# TCC_modulo_de_automa_o_Wifi_Rev_2.net
KiCad netlist of a schematic drawn in EAGLE
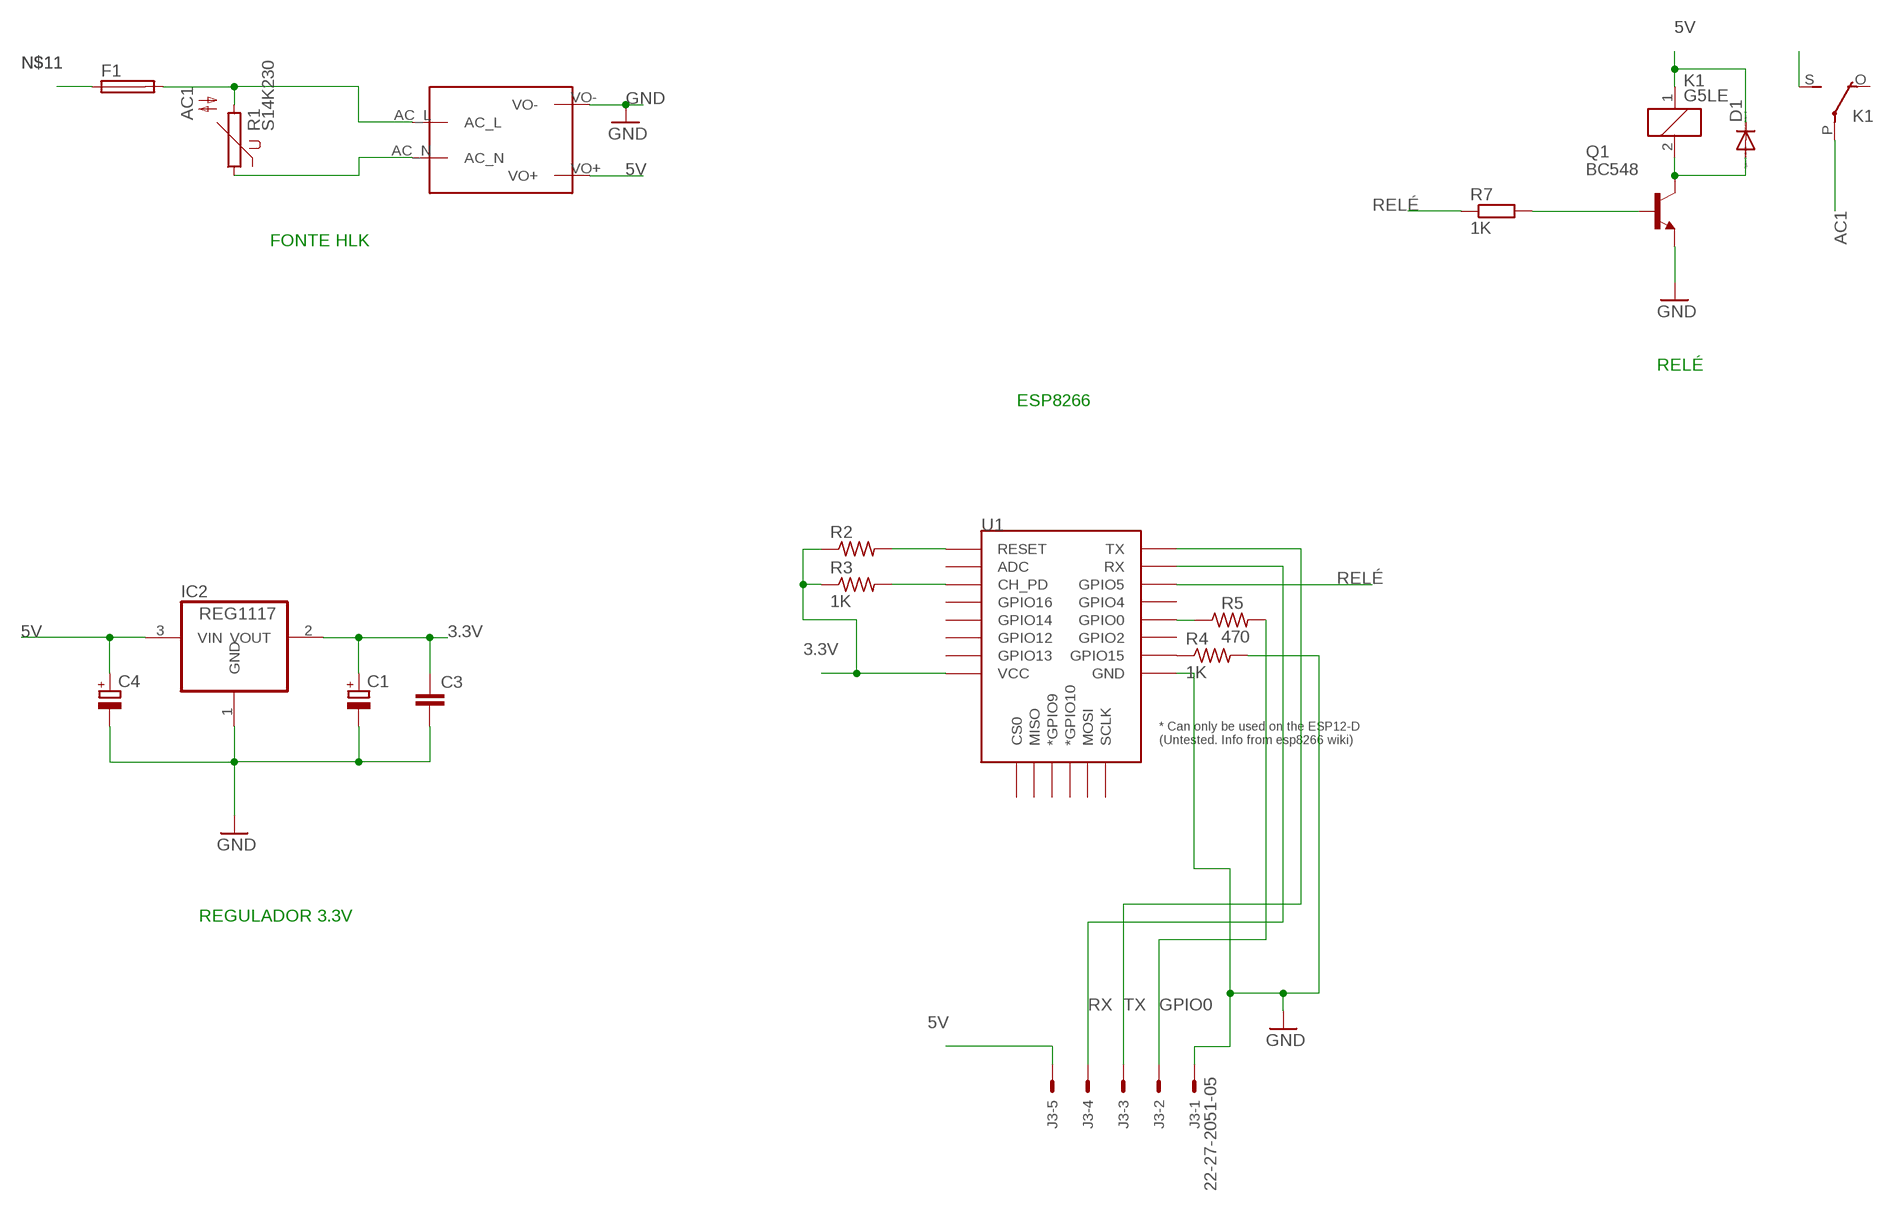
[diagram p0: schematic, sheet 1]

(export (version "E")
  (design (tool "Eeschema 10.0.6"))
  (components
    (comp (ref "C1")
      (value "CPOL-EU153CLV-0505")
      (footprint "eagle-import:153CLV-0505")
      (libsource (lib "eagle-import") (part "CPOL-EU153CLV-0505"))
    )
    (comp (ref "C3")
      (value "C-EUC0805")
      (footprint "eagle-import:C0805")
      (libsource (lib "eagle-import") (part "C-EUC0805"))
    )
    (comp (ref "C4")
      (value "CPOL-EUC/6032-28R")
      (footprint "eagle-import:C_6032-28R")
      (libsource (lib "eagle-import") (part "CPOL-EUC/6032-28R"))
    )
    (comp (ref "D1")
      (value "DIODE-SOD106A-R")
      (footprint "eagle-import:SOD106A-R")
      (libsource (lib "eagle-import") (part "DIODE-SOD106A-R"))
    )
    (comp (ref "F1")
      (value "SH22")
      (footprint "eagle-import:SH22")
      (libsource (lib "eagle-import") (part "SH22"))
    )
    (comp (ref "IC2")
      (value "REG1117")
      (footprint "eagle-import:SOT223")
      (libsource (lib "eagle-import") (part "REG1117"))
    )
    (comp (ref "J3")
      (value "22-27-2051-05")
      (footprint "eagle-import:6410-05")
      (libsource (lib "eagle-import") (part "22-?-0527-2051"))
    )
    (comp (ref "K1")
      (value "G5LE")
      (footprint "eagle-import:G5LE")
      (libsource (lib "eagle-import") (part "G5LE"))
    )
    (comp (ref "Q1")
      (value "BC548")
      (footprint "eagle-import:TO92-EBC")
      (libsource (lib "eagle-import") (part "BC548"))
    )
    (comp (ref "R1")
      (value "S14K230")
      (footprint "eagle-import:S14K230")
      (libsource (lib "eagle-import") (part "S14K230"))
    )
    (comp (ref "R2")
      (value "R-US_M0805")
      (footprint "eagle-import:M0805")
      (libsource (lib "eagle-import") (part "R-US_M0805"))
    )
    (comp (ref "R3")
      (value "1K")
      (footprint "eagle-import:M0805")
      (libsource (lib "eagle-import") (part "R-US_M0805"))
    )
    (comp (ref "R4")
      (value "1K")
      (footprint "eagle-import:M0805")
      (libsource (lib "eagle-import") (part "R-US_M0805"))
    )
    (comp (ref "R5")
      (value "470")
      (footprint "eagle-import:M0805")
      (libsource (lib "eagle-import") (part "R-US_M0805"))
    )
    (comp (ref "R7")
      (value "1K")
      (footprint "eagle-import:M0805")
      (libsource (lib "eagle-import") (part "R-EU_M0805"))
    )
    (comp (ref "U$2")
      (value "MAINS_CONVERTERS")
      (footprint "eagle-import:HLK-PM01")
      (libsource (lib "eagle-import") (part "MAINS_CONVERTERS"))
    )
    (comp (ref "U1")
      (value "ESP12ESMD")
      (footprint "eagle-import:ESP12E-SMD")
      (libsource (lib "eagle-import") (part "ESP12ESMD"))
    )
  )
  (nets
    (net (code "1") (name "/3.3V") (class "Default")
      (node (ref "C1") (pin "+") (pinfunction "+_+") (pintype "passive"))
      (node (ref "C3") (pin "1") (pinfunction "1_1") (pintype "passive"))
      (node (ref "IC2") (pin "2") (pinfunction "VOUT_2") (pintype "output"))
      (node (ref "R2") (pin "1") (pinfunction "1_1") (pintype "passive"))
      (node (ref "R3") (pin "1") (pinfunction "1_1") (pintype "passive"))
      (node (ref "U1") (pin "VCC") (pinfunction "VCC_VCC") (pintype "bidirectional"))
    )
    (net (code "2") (name "/5V") (class "Default")
      (node (ref "C4") (pin "+") (pinfunction "+_+") (pintype "passive"))
      (node (ref "D1") (pin "C") (pinfunction "C_C") (pintype "passive"))
      (node (ref "IC2") (pin "3") (pinfunction "VIN_3") (pintype "input"))
      (node (ref "J3") (pin "5") (pinfunction "S_5") (pintype "passive"))
      (node (ref "K1") (pin "1") (pinfunction "1_1") (pintype "passive"))
      (node (ref "U$2") (pin "VO+") (pinfunction "VO+_VO+") (pintype "output"))
    )
    (net (code "3") (name "/AC1") (class "Default")
      (node (ref "F1") (pin "2") (pinfunction "2_2") (pintype "passive"))
      (node (ref "K1") (pin "P") (pinfunction "P_P") (pintype "passive"))
      (node (ref "R1") (pin "2") (pinfunction "2_2") (pintype "passive"))
      (node (ref "U$2") (pin "AC_L") (pinfunction "AC_L_AC_L") (pintype "input"))
    )
    (net (code "4") (name "/GPIO0") (class "Default")
      (node (ref "J3") (pin "2") (pinfunction "S_2") (pintype "passive"))
      (node (ref "R5") (pin "2") (pinfunction "2_2") (pintype "passive"))
    )
    (net (code "5") (name "/N$11") (class "Default")
      (node (ref "F1") (pin "1") (pinfunction "1_1") (pintype "passive"))
    )
    (net (code "6") (name "/RELÉ") (class "Default")
      (node (ref "R7") (pin "1") (pinfunction "1_1") (pintype "passive"))
      (node (ref "U1") (pin "GPIO5") (pinfunction "GPIO5_GPIO5") (pintype "bidirectional"))
    )
    (net (code "7") (name "/RX") (class "Default")
      (node (ref "J3") (pin "4") (pinfunction "S_4") (pintype "passive"))
      (node (ref "U1") (pin "RXD0") (pinfunction "RX_RXD0") (pintype "bidirectional"))
    )
    (net (code "8") (name "/TX") (class "Default")
      (node (ref "J3") (pin "3") (pinfunction "S_3") (pintype "passive"))
      (node (ref "U1") (pin "TXD0") (pinfunction "TX_TXD0") (pintype "bidirectional"))
    )
    (net (code "9") (name "GND") (class "Default")
      (node (ref "C1") (pin "-") (pinfunction "-_-") (pintype "passive"))
      (node (ref "C3") (pin "2") (pinfunction "2_2") (pintype "passive"))
      (node (ref "C4") (pin "-") (pinfunction "-_-") (pintype "passive"))
      (node (ref "IC2") (pin "1") (pinfunction "GND_1") (pintype "power_in"))
      (node (ref "J3") (pin "1") (pinfunction "S_1") (pintype "passive"))
      (node (ref "Q1") (pin "E") (pinfunction "E_E") (pintype "passive"))
      (node (ref "R4") (pin "2") (pinfunction "2_2") (pintype "passive"))
      (node (ref "U$2") (pin "VO-") (pinfunction "VO-_VO-") (pintype "output"))
      (node (ref "U1") (pin "GND") (pinfunction "GND_GND") (pintype "bidirectional"))
    )
    (net (code "10") (name "Net-(D1-PadA)") (class "Default")
      (node (ref "D1") (pin "A") (pinfunction "A_A") (pintype "passive"))
      (node (ref "K1") (pin "2") (pinfunction "2_2") (pintype "passive"))
      (node (ref "Q1") (pin "C") (pinfunction "C_C") (pintype "passive"))
    )
    (net (code "11") (name "Net-(Q1-PadB)") (class "Default")
      (node (ref "Q1") (pin "B") (pinfunction "B_B") (pintype "passive"))
      (node (ref "R7") (pin "2") (pinfunction "2_2") (pintype "passive"))
    )
    (net (code "12") (name "Net-(R1-Pad1)") (class "Default")
      (node (ref "R1") (pin "1") (pinfunction "1_1") (pintype "passive"))
      (node (ref "U$2") (pin "AC_N") (pinfunction "AC_N_AC_N") (pintype "input"))
    )
    (net (code "13") (name "Net-(R2-Pad2)") (class "Default")
      (node (ref "R2") (pin "2") (pinfunction "2_2") (pintype "passive"))
      (node (ref "U1") (pin "RESET") (pinfunction "RESET_RESET") (pintype "bidirectional"))
    )
    (net (code "14") (name "Net-(R3-Pad2)") (class "Default")
      (node (ref "R3") (pin "2") (pinfunction "2_2") (pintype "passive"))
      (node (ref "U1") (pin "CH_PD") (pinfunction "CH_PD_CH_PD") (pintype "bidirectional"))
    )
    (net (code "15") (name "Net-(R4-Pad1)") (class "Default")
      (node (ref "R4") (pin "1") (pinfunction "1_1") (pintype "passive"))
      (node (ref "U1") (pin "GPIO15") (pinfunction "GPIO15_GPIO15") (pintype "bidirectional"))
    )
    (net (code "16") (name "Net-(R5-Pad1)") (class "Default")
      (node (ref "R5") (pin "1") (pinfunction "1_1") (pintype "passive"))
      (node (ref "U1") (pin "GPIO0") (pinfunction "GPIO0_GPIO0") (pintype "bidirectional"))
    )
    (net (code "17") (name "unconnected-(K1-PadO)") (class "Default")
      (node (ref "K1") (pin "O") (pinfunction "O_O") (pintype "passive"))
    )
    (net (code "18") (name "unconnected-(K1-PadS)") (class "Default")
      (node (ref "K1") (pin "S") (pinfunction "S_S") (pintype "passive"))
    )
    (net (code "19") (name "unconnected-(U1-*GPIO9-PadGPIO9)") (class "Default")
      (node (ref "U1") (pin "GPIO9") (pinfunction "*GPIO9_GPIO9") (pintype "bidirectional"))
    )
    (net (code "20") (name "unconnected-(U1-*GPIO10-PadGPIO10)") (class "Default")
      (node (ref "U1") (pin "GPIO10") (pinfunction "*GPIO10_GPIO10") (pintype "bidirectional"))
    )
    (net (code "21") (name "unconnected-(U1-PadADC)") (class "Default")
      (node (ref "U1") (pin "ADC") (pinfunction "ADC_ADC") (pintype "bidirectional"))
    )
    (net (code "22") (name "unconnected-(U1-PadCS0)") (class "Default")
      (node (ref "U1") (pin "CS0") (pinfunction "CS0_CS0") (pintype "bidirectional"))
    )
    (net (code "23") (name "unconnected-(U1-PadGPIO2)") (class "Default")
      (node (ref "U1") (pin "GPIO2") (pinfunction "GPIO2_GPIO2") (pintype "bidirectional"))
    )
    (net (code "24") (name "unconnected-(U1-PadGPIO4)") (class "Default")
      (node (ref "U1") (pin "GPIO4") (pinfunction "GPIO4_GPIO4") (pintype "bidirectional"))
    )
    (net (code "25") (name "unconnected-(U1-PadGPIO12)") (class "Default")
      (node (ref "U1") (pin "GPIO12") (pinfunction "GPIO12_GPIO12") (pintype "bidirectional"))
    )
    (net (code "26") (name "unconnected-(U1-PadGPIO13)") (class "Default")
      (node (ref "U1") (pin "GPIO13") (pinfunction "GPIO13_GPIO13") (pintype "bidirectional"))
    )
    (net (code "27") (name "unconnected-(U1-PadGPIO14)") (class "Default")
      (node (ref "U1") (pin "GPIO14") (pinfunction "GPIO14_GPIO14") (pintype "bidirectional"))
    )
    (net (code "28") (name "unconnected-(U1-PadGPIO16)") (class "Default")
      (node (ref "U1") (pin "GPIO16") (pinfunction "GPIO16_GPIO16") (pintype "bidirectional"))
    )
    (net (code "29") (name "unconnected-(U1-PadMISO)") (class "Default")
      (node (ref "U1") (pin "MISO") (pinfunction "MISO_MISO") (pintype "bidirectional"))
    )
    (net (code "30") (name "unconnected-(U1-PadMOSI)") (class "Default")
      (node (ref "U1") (pin "MOSI") (pinfunction "MOSI_MOSI") (pintype "bidirectional"))
    )
    (net (code "31") (name "unconnected-(U1-PadSCLK)") (class "Default")
      (node (ref "U1") (pin "SCLK") (pinfunction "SCLK_SCLK") (pintype "bidirectional"))
    )
  )
)
